# SAMD_Test_Board.net
KiCad netlist of a schematic drawn in EAGLE
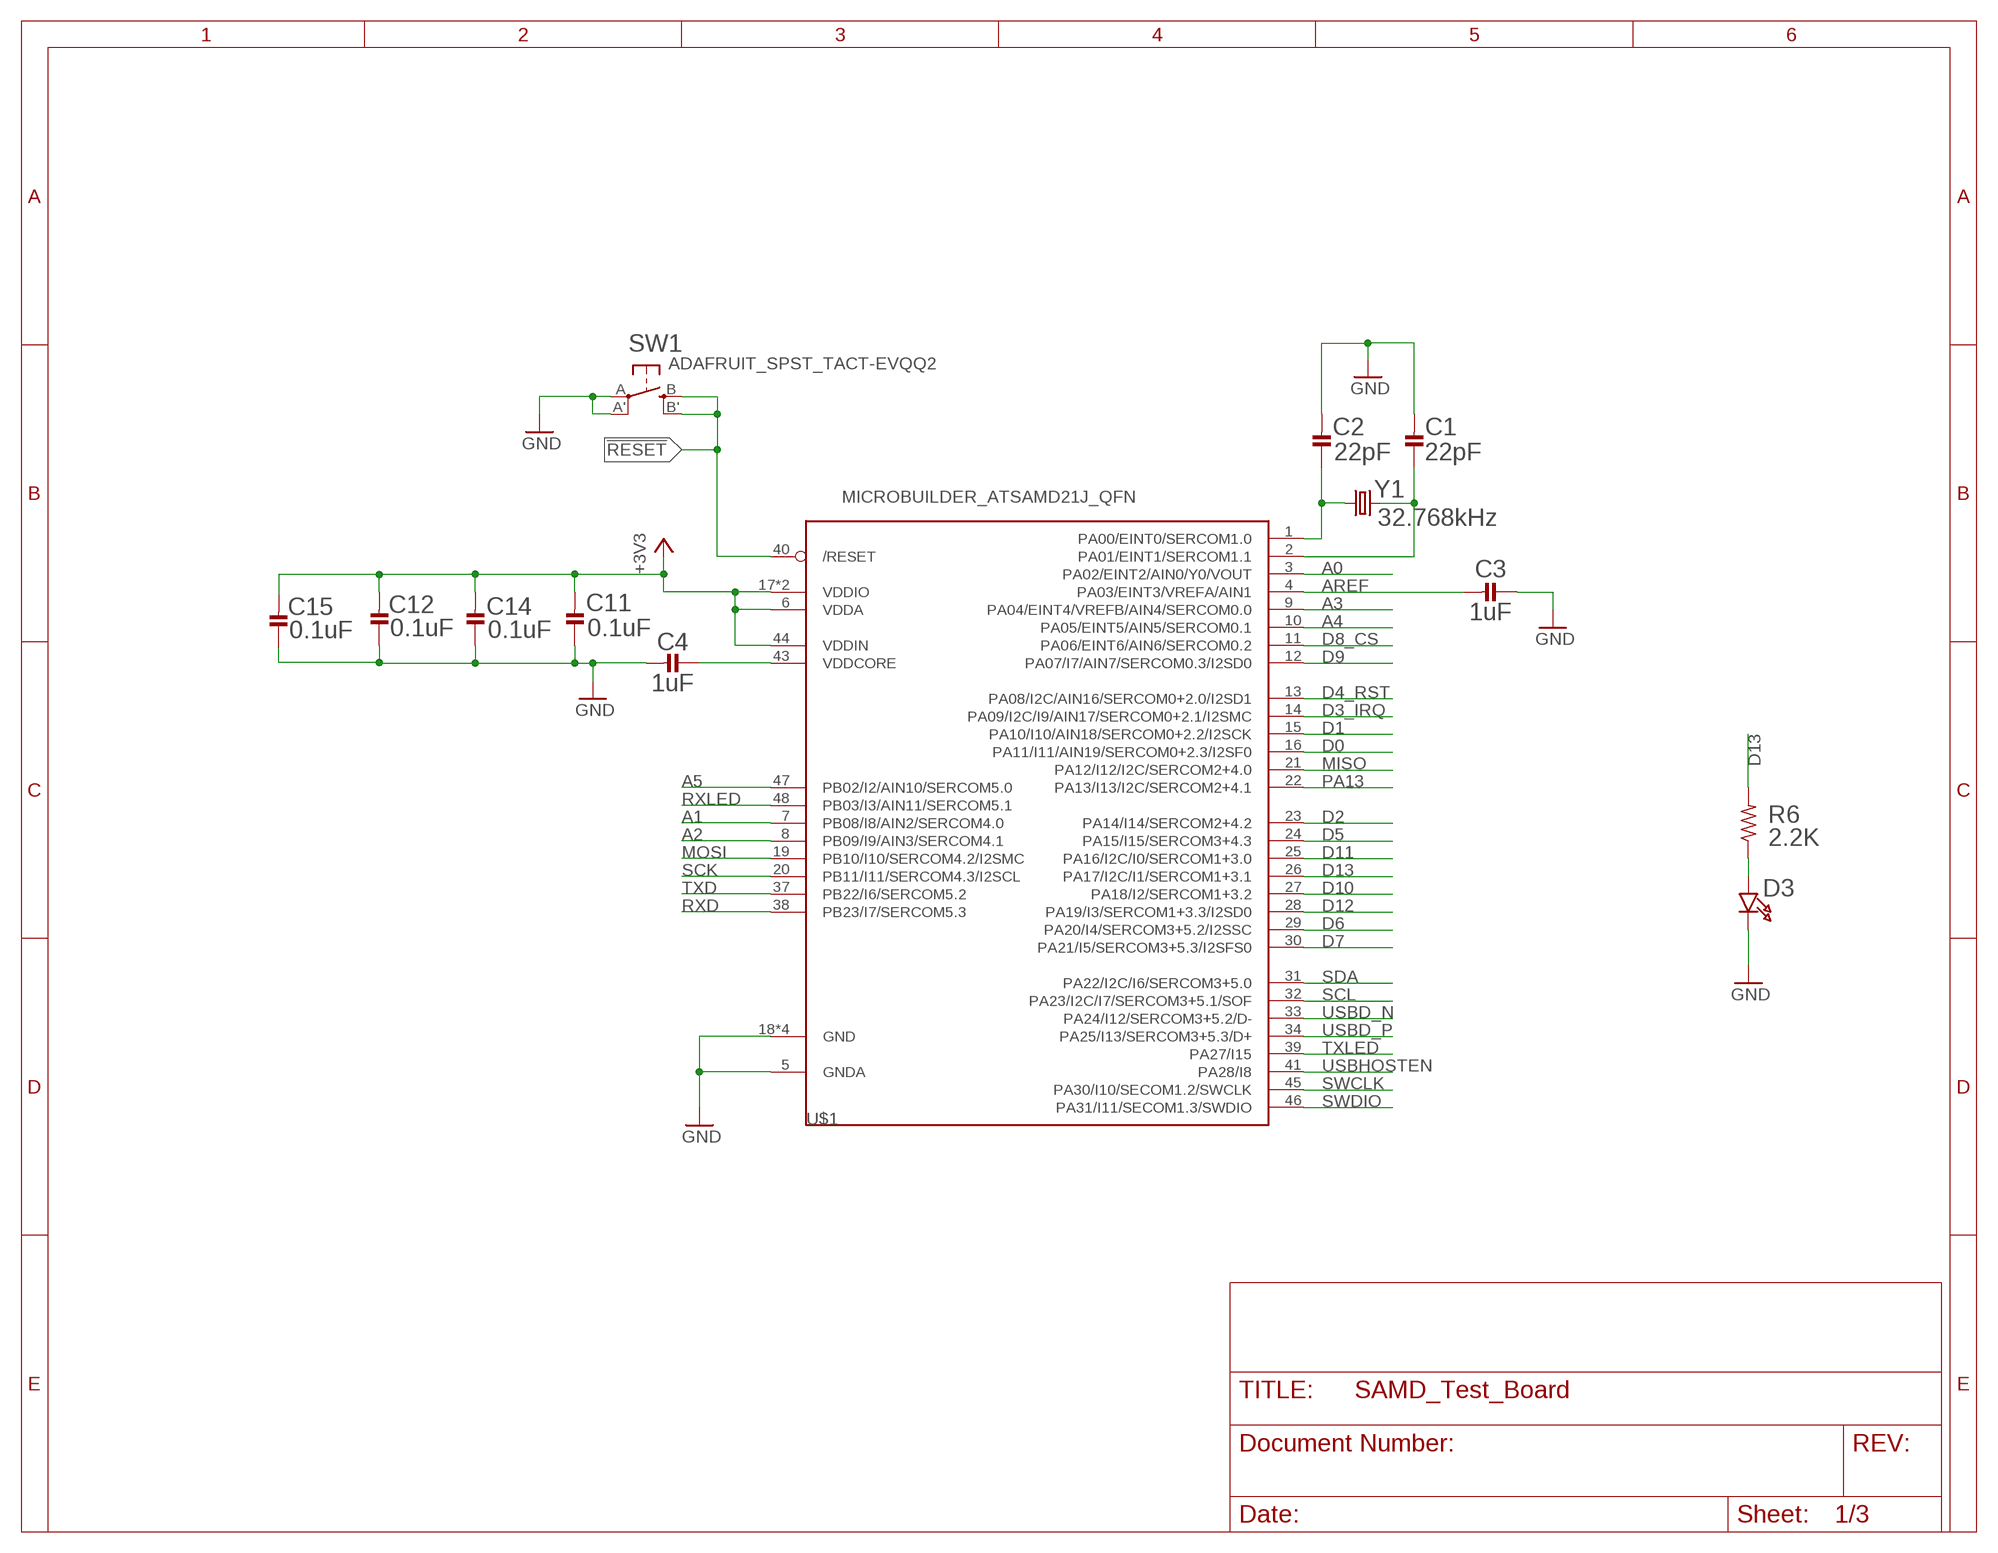
[diagram p0: schematic, sheet 1]
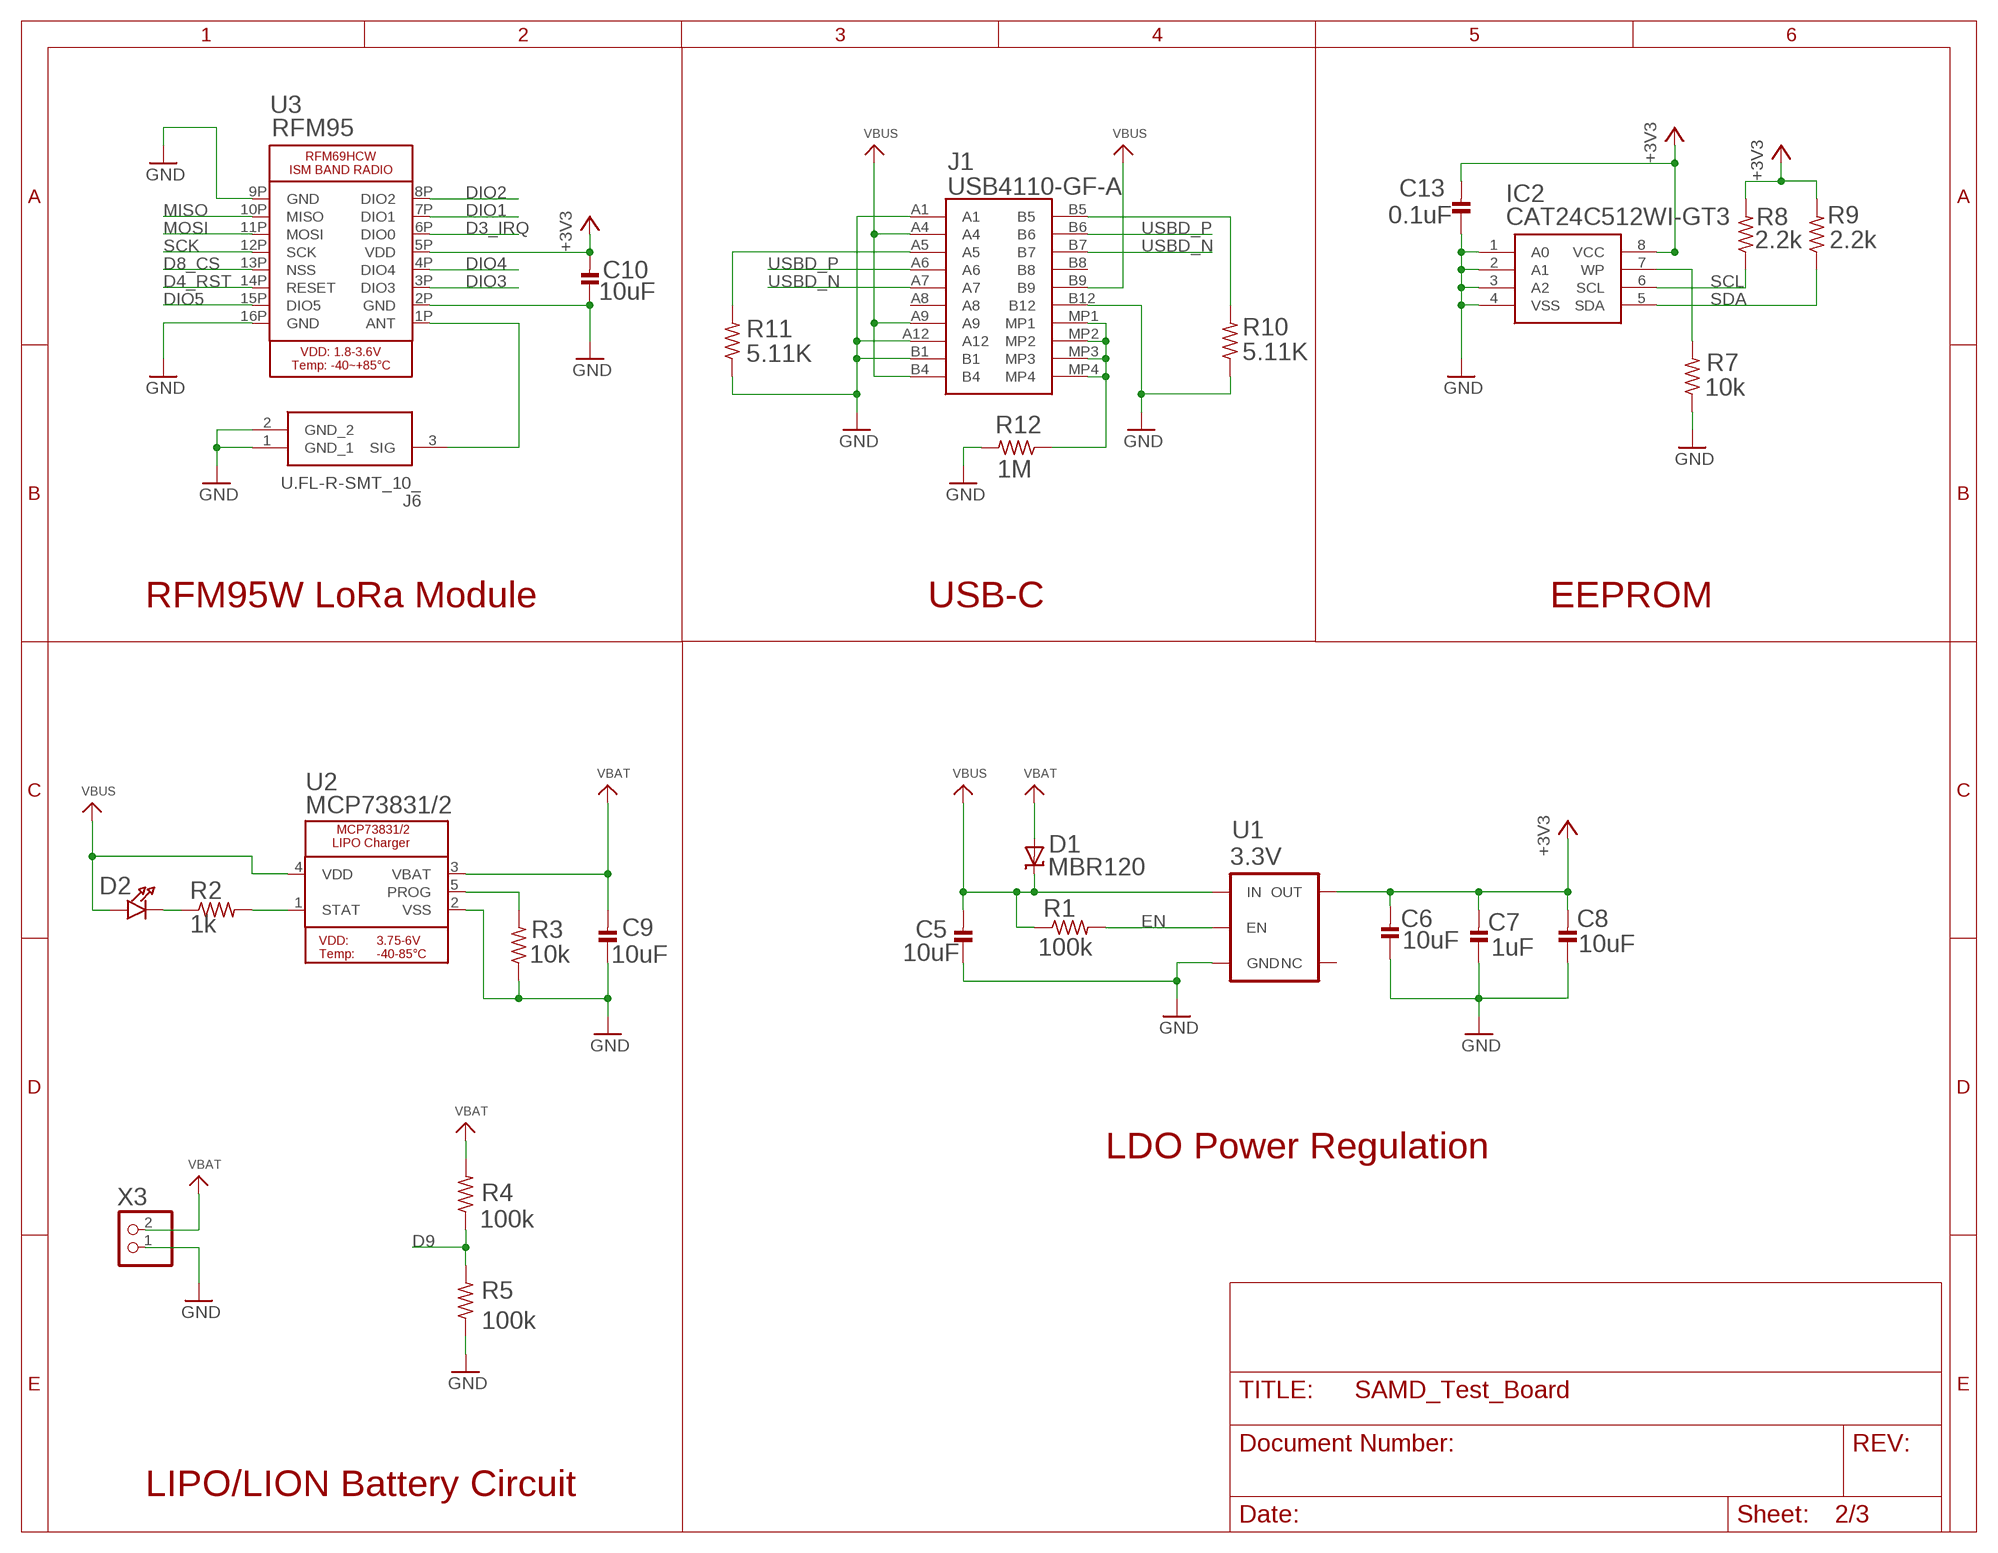
[diagram p1: schematic, sheet 2]
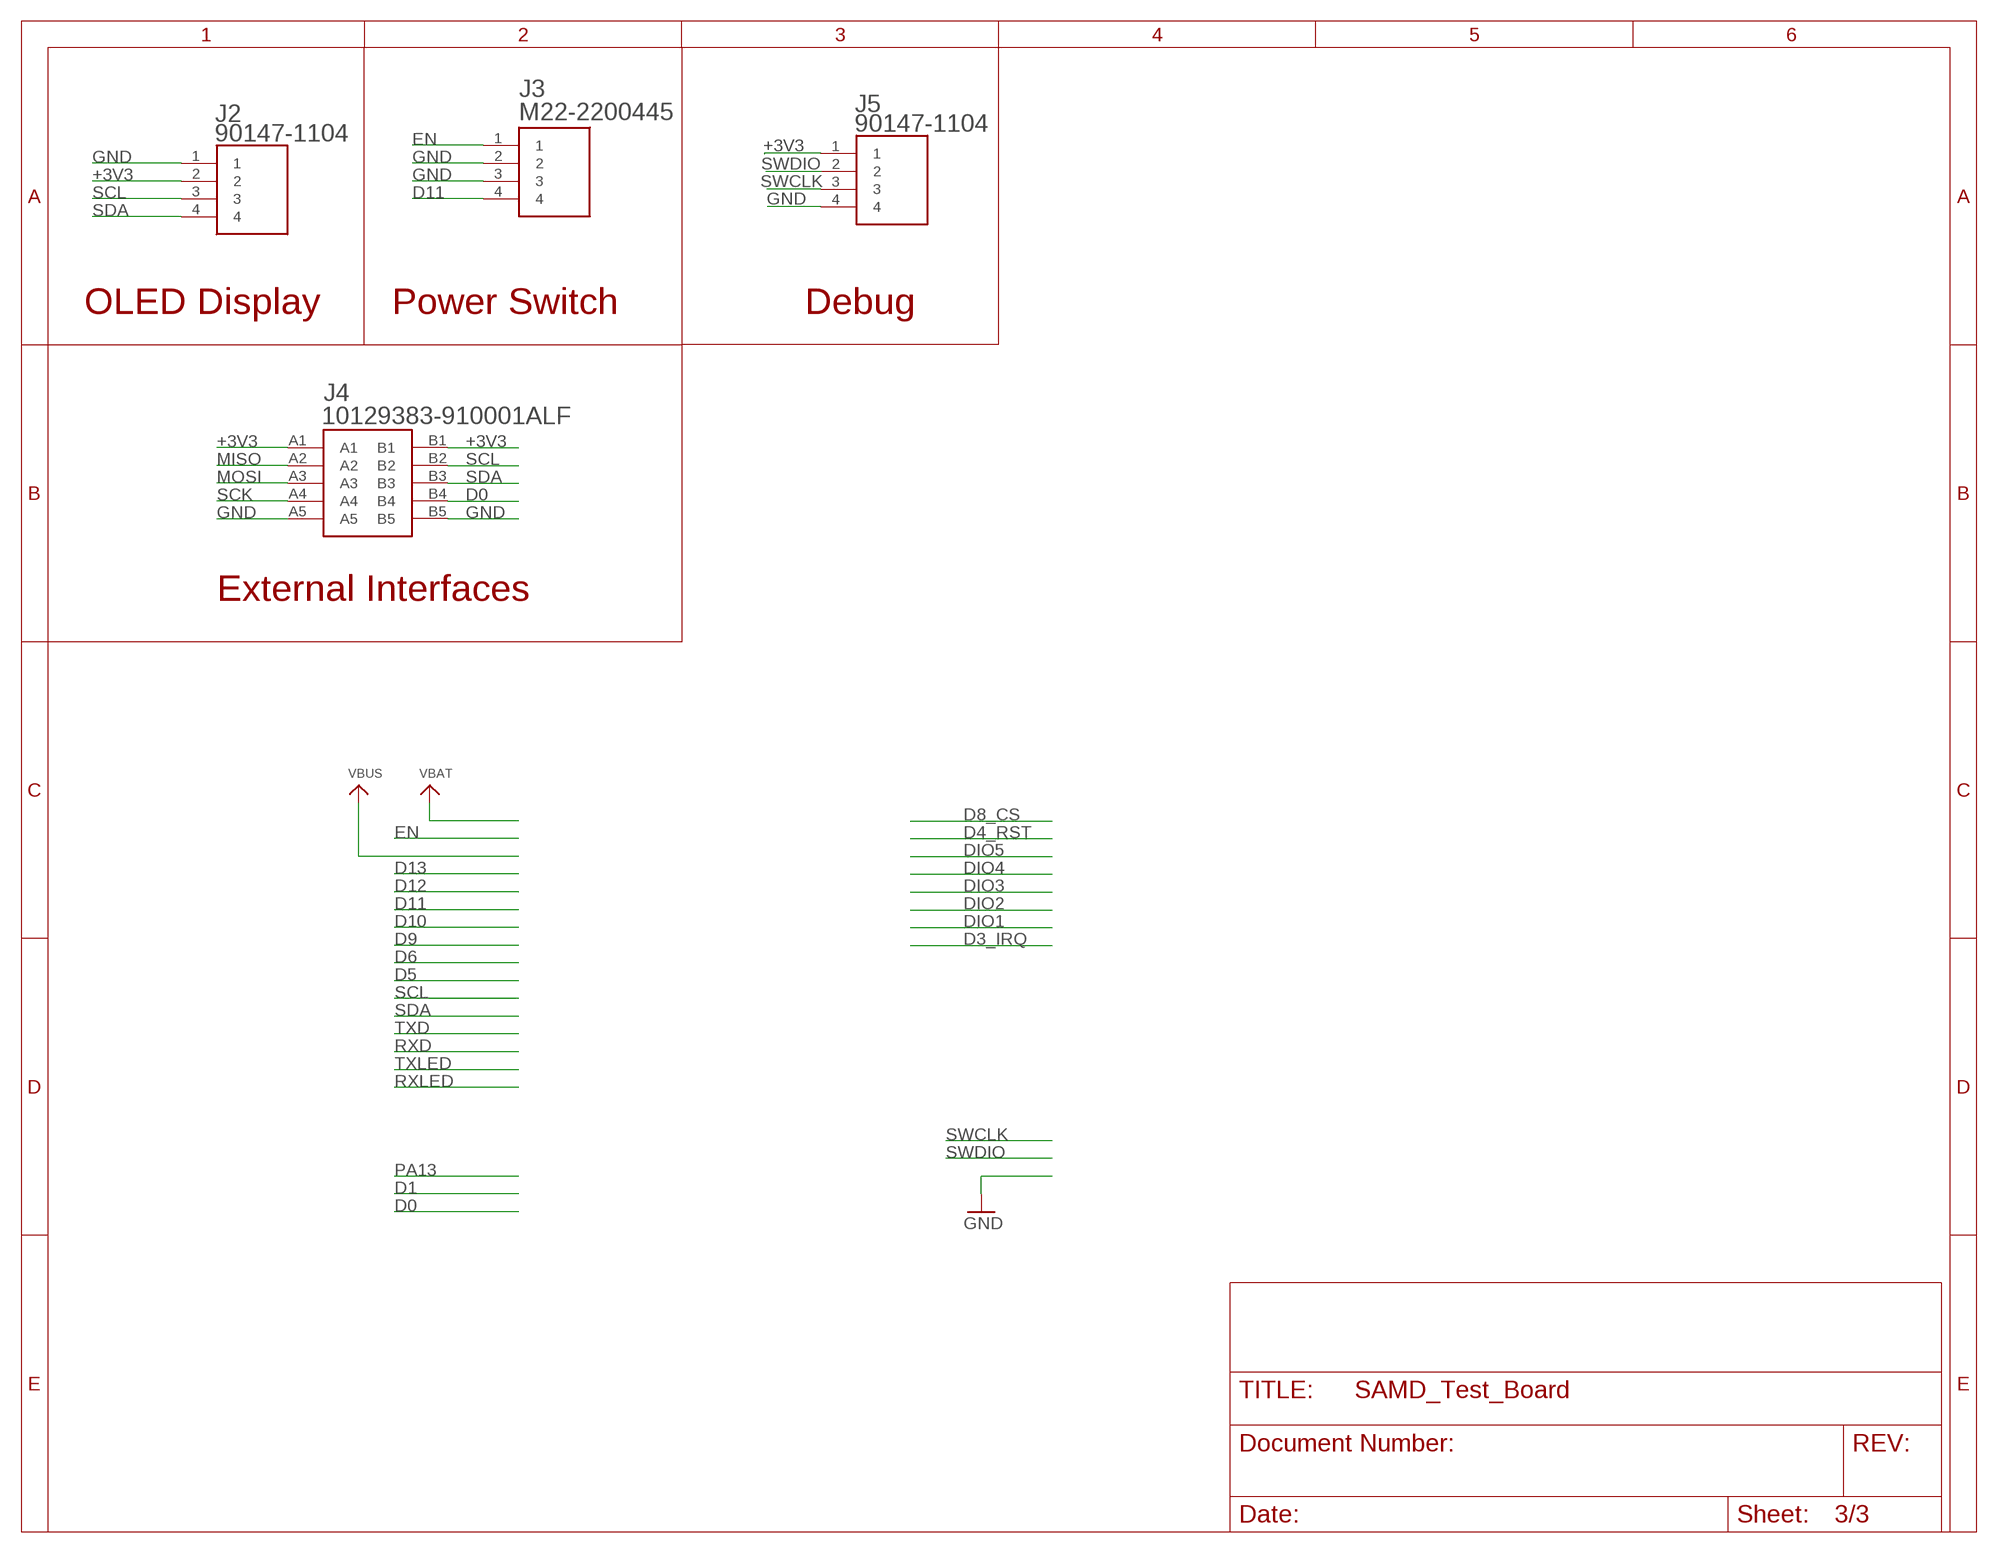
[diagram p2: schematic, sheet 3]

(export (version "E")
  (design (tool "Eeschema 10.0.6"))
  (components
    (comp (ref "C1")
      (value "22pF")
      (footprint "eagle-import:MICROBUILDER__0805")
      (libsource (lib "eagle-import") (part "MICROBUILDER_CAP_CERAMIC_0805"))
    )
    (comp (ref "C2")
      (value "22pF")
      (footprint "eagle-import:MICROBUILDER__0805")
      (libsource (lib "eagle-import") (part "MICROBUILDER_CAP_CERAMIC_0805"))
    )
    (comp (ref "C3")
      (value "1uF")
      (footprint "eagle-import:MICROBUILDER__0805")
      (libsource (lib "eagle-import") (part "MICROBUILDER_CAP_CERAMIC_0805"))
    )
    (comp (ref "C4")
      (value "1uF")
      (footprint "eagle-import:MICROBUILDER__0805")
      (libsource (lib "eagle-import") (part "MICROBUILDER_CAP_CERAMIC_0805"))
    )
    (comp (ref "C11")
      (value "0.1uF")
      (footprint "eagle-import:MICROBUILDER__0805")
      (libsource (lib "eagle-import") (part "MICROBUILDER_CAP_CERAMIC_0805"))
    )
    (comp (ref "C12")
      (value "0.1uF")
      (footprint "eagle-import:MICROBUILDER__0805")
      (libsource (lib "eagle-import") (part "MICROBUILDER_CAP_CERAMIC_0805"))
    )
    (comp (ref "C14")
      (value "0.1uF")
      (footprint "eagle-import:MICROBUILDER__0805")
      (libsource (lib "eagle-import") (part "MICROBUILDER_CAP_CERAMIC_0805"))
    )
    (comp (ref "C15")
      (value "0.1uF")
      (footprint "eagle-import:MICROBUILDER__0805")
      (libsource (lib "eagle-import") (part "MICROBUILDER_CAP_CERAMIC_0805"))
    )
    (comp (ref "D3")
      (value "MICROBUILDER_LED0603")
      (footprint "eagle-import:MICROBUILDER_CHIPLED_0603")
      (libsource (lib "eagle-import") (part "MICROBUILDER_LED0603"))
    )
    (comp (ref "R6")
      (value "2.2K")
      (footprint "eagle-import:R0805")
      (libsource (lib "eagle-import") (part "R-US_R0805"))
    )
    (comp (ref "SW1")
      (value "ADAFRUIT_SPST_TACT-EVQQ2")
      (footprint "eagle-import:ADAFRUIT_EVQ-Q2")
      (libsource (lib "eagle-import") (part "ADAFRUIT_SPST_TACT-EVQQ2"))
    )
    (comp (ref "U$1")
      (value "MICROBUILDER_ATSAMD21J_QFN")
      (footprint "eagle-import:MICROBUILDER_TQFN48_7MM")
      (libsource (lib "eagle-import") (part "MICROBUILDER_ATSAMD21J_QFN"))
    )
    (comp (ref "Y1")
      (value "32.768kHz")
      (footprint "eagle-import:CRYSTAL-SMD-3.2X1.5MM")
      (libsource (lib "eagle-import") (part "CRYSTAL-32.768KHZSMD-3.2X1.5"))
    )
    (comp (ref "C5")
      (value "10uF")
      (footprint "eagle-import:MICROBUILDER__0805")
      (libsource (lib "eagle-import") (part "MICROBUILDER_CAP_CERAMIC_0805"))
    )
    (comp (ref "C6")
      (value "10uF")
      (footprint "eagle-import:MICROBUILDER__0805")
      (libsource (lib "eagle-import") (part "MICROBUILDER_CAP_CERAMIC_0805"))
    )
    (comp (ref "C7")
      (value "1uF")
      (footprint "eagle-import:MICROBUILDER__0805")
      (libsource (lib "eagle-import") (part "MICROBUILDER_CAP_CERAMIC_0805"))
    )
    (comp (ref "C8")
      (value "10uF")
      (footprint "eagle-import:MICROBUILDER__0805")
      (libsource (lib "eagle-import") (part "MICROBUILDER_CAP_CERAMIC_0805"))
    )
    (comp (ref "C9")
      (value "10uF")
      (footprint "eagle-import:MICROBUILDER__0805")
      (libsource (lib "eagle-import") (part "MICROBUILDER_CAP_CERAMIC_0805"))
    )
    (comp (ref "C10")
      (value "10uF")
      (footprint "eagle-import:MICROBUILDER__0805")
      (libsource (lib "eagle-import") (part "MICROBUILDER_CAP_CERAMIC_0805"))
    )
    (comp (ref "C13")
      (value "0.1uF")
      (footprint "eagle-import:MICROBUILDER__0805")
      (libsource (lib "eagle-import") (part "MICROBUILDER_CAP_CERAMIC_0805"))
    )
    (comp (ref "D1")
      (value "MBR120")
      (footprint "eagle-import:MICROBUILDER_SOD-123")
      (libsource (lib "eagle-import") (part "MICROBUILDER_DIODE-SCHOTTKYSOD-123"))
    )
    (comp (ref "D2")
      (value "MICROBUILDER_LED0603")
      (footprint "eagle-import:MICROBUILDER_CHIPLED_0603")
      (libsource (lib "eagle-import") (part "MICROBUILDER_LED0603"))
    )
    (comp (ref "IC2")
      (value "CAT24C512WI-GT3")
      (footprint "eagle-import:SOIC127P600X175-8N")
      (fields (field (name "MOUSER_PART_NUMBER") "863-CAT24C512WI-GT3"))
      (libsource (lib "eagle-import") (part "CAT24C512WI-GT3"))
    )
    (comp (ref "J1")
      (value "USB4110-GF-A")
      (footprint "eagle-import:USB4110GFA")
      (fields (field (name "MOUSER_PART_NUMBER") "640-USB4110-GF-A"))
      (libsource (lib "eagle-import") (part "USB4110-GF-A"))
    )
    (comp (ref "J6")
      (value "U.FL-R-SMT_10_")
      (footprint "eagle-import:UFLRSMT10")
      (fields
        (field (name "MANUFACTURER_PART_NUMBER") "U.FL-R-SMT(10)")
        (field (name "MOUSER_PART_NUMBER") "798-U.FL-R-SMT10")
      )
      (libsource (lib "eagle-import") (part "U.FL-R-SMT_10_"))
    )
    (comp (ref "R1")
      (value "100k")
      (footprint "eagle-import:R0805")
      (libsource (lib "eagle-import") (part "R-US_R0805"))
    )
    (comp (ref "R2")
      (value "1k")
      (footprint "eagle-import:R0805")
      (libsource (lib "eagle-import") (part "R-US_R0805"))
    )
    (comp (ref "R3")
      (value "10k")
      (footprint "eagle-import:R0805")
      (libsource (lib "eagle-import") (part "R-US_R0805"))
    )
    (comp (ref "R4")
      (value "100k")
      (footprint "eagle-import:R0805")
      (libsource (lib "eagle-import") (part "R-US_R0805"))
    )
    (comp (ref "R5")
      (value "100k")
      (footprint "eagle-import:R0805")
      (libsource (lib "eagle-import") (part "R-US_R0805"))
    )
    (comp (ref "R7")
      (value "10k")
      (footprint "eagle-import:R0805")
      (libsource (lib "eagle-import") (part "R-US_R0805"))
    )
    (comp (ref "R8")
      (value "2.2k")
      (footprint "eagle-import:R0805")
      (libsource (lib "eagle-import") (part "R-US_R0805"))
    )
    (comp (ref "R9")
      (value "2.2k")
      (footprint "eagle-import:R0805")
      (libsource (lib "eagle-import") (part "R-US_R0805"))
    )
    (comp (ref "R10")
      (value "5.11K")
      (footprint "eagle-import:R0805")
      (libsource (lib "eagle-import") (part "R-US_R0805"))
    )
    (comp (ref "R11")
      (value "5.11K")
      (footprint "eagle-import:R0805")
      (libsource (lib "eagle-import") (part "R-US_R0805"))
    )
    (comp (ref "R12")
      (value "1M")
      (footprint "eagle-import:R0805")
      (libsource (lib "eagle-import") (part "R-US_R0805"))
    )
    (comp (ref "U1")
      (value "3.3V")
      (footprint "eagle-import:SOT23-5")
      (libsource (lib "eagle-import") (part "V_REG_AP2112K-3.3V"))
    )
    (comp (ref "U2")
      (value "MCP73831/2")
      (footprint "eagle-import:MICROBUILDER_SOT23-5")
      (libsource (lib "eagle-import") (part "MICROBUILDER_MCP73831/2"))
    )
    (comp (ref "U3")
      (value "RFM95")
      (footprint "eagle-import:MICROBUILDER_RFMHCW_SMT")
      (libsource (lib "eagle-import") (part "MICROBUILDER_RFM69HCW_SMT"))
    )
    (comp (ref "X3")
      (value "MICROBUILDER_CON_JST_PH_2PIN")
      (footprint "eagle-import:MICROBUILDER_JSTPH2")
      (libsource (lib "eagle-import") (part "MICROBUILDER_CON_JST_PH_2PIN"))
    )
    (comp (ref "J2")
      (value "90147-1104")
      (footprint "eagle-import:RHDR4W70P0X254_1X4_1016X244X87")
      (fields (field (name "MOUSER_PART_NUMBER") "538-90147-1104"))
      (libsource (lib "eagle-import") (part "90147-1104"))
    )
    (comp (ref "J3")
      (value "M22-2200445")
      (footprint "eagle-import:SHDR4W50P0X200_1X4_1000X470X63")
      (fields (field (name "MOUSER_PART_NUMBER") "855-M22-2200445"))
      (libsource (lib "eagle-import") (part "M22-2200445"))
    )
    (comp (ref "J4")
      (value "10129383-910001ALF")
      (footprint "eagle-import:10129383910001ALF")
      (fields (field (name "MOUSER_PART_NUMBER") "649-1012938391001ALF"))
      (libsource (lib "eagle-import") (part "10129383-910001ALF"))
    )
    (comp (ref "J5")
      (value "90147-1104")
      (footprint "eagle-import:RHDR4W70P0X254_1X4_1016X244X87")
      (fields (field (name "MOUSER_PART_NUMBER") "538-90147-1104"))
      (libsource (lib "eagle-import") (part "90147-1104"))
    )
  )
  (nets
    (net (code "1") (name "+3V3") (class "Default")
      (node (ref "C10") (pin "2") (pinfunction "2_2") (pintype "passive"))
      (node (ref "C11") (pin "2") (pinfunction "2_2") (pintype "passive"))
      (node (ref "C12") (pin "2") (pinfunction "2_2") (pintype "passive"))
      (node (ref "C13") (pin "2") (pinfunction "2_2") (pintype "passive"))
      (node (ref "C14") (pin "2") (pinfunction "2_2") (pintype "passive"))
      (node (ref "C15") (pin "2") (pinfunction "2_2") (pintype "passive"))
      (node (ref "C6") (pin "2") (pinfunction "2_2") (pintype "passive"))
      (node (ref "C7") (pin "2") (pinfunction "2_2") (pintype "passive"))
      (node (ref "C8") (pin "2") (pinfunction "2_2") (pintype "passive"))
      (node (ref "IC2") (pin "8") (pinfunction "VCC_8") (pintype "power_in"))
      (node (ref "J2") (pin "2") (pinfunction "2_2") (pintype "bidirectional"))
      (node (ref "J4") (pin "A1") (pinfunction "A1_A1") (pintype "bidirectional"))
      (node (ref "J4") (pin "B1") (pinfunction "B1_B1") (pintype "bidirectional"))
      (node (ref "J5") (pin "1") (pinfunction "1_1") (pintype "bidirectional"))
      (node (ref "R8") (pin "2") (pinfunction "2_2") (pintype "passive"))
      (node (ref "R9") (pin "2") (pinfunction "2_2") (pintype "passive"))
      (node (ref "U$1") (pin "17") (pinfunction "VDDIO_17") (pintype "power_in"))
      (node (ref "U$1") (pin "36") (pinfunction "VDDIO_36") (pintype "power_in"))
      (node (ref "U$1") (pin "44") (pinfunction "VDDIN_44") (pintype "power_in"))
      (node (ref "U$1") (pin "6") (pinfunction "VDDA_6") (pintype "power_in"))
      (node (ref "U1") (pin "5") (pinfunction "OUT_5") (pintype "passive"))
      (node (ref "U3") (pin "5P") (pinfunction "VDD_5P") (pintype "power_in"))
    )
    (net (code "2") (name "A0") (class "Default")
      (node (ref "U$1") (pin "3") (pinfunction "PA02/EINT2/AIN0/Y0/VOUT_3") (pintype "bidirectional"))
    )
    (net (code "3") (name "A1") (class "Default")
      (node (ref "U$1") (pin "7") (pinfunction "PB08/I8/AIN2/SERCOM4.0_7") (pintype "bidirectional"))
    )
    (net (code "4") (name "A2") (class "Default")
      (node (ref "U$1") (pin "8") (pinfunction "PB09/I9/AIN3/SERCOM4.1_8") (pintype "bidirectional"))
    )
    (net (code "5") (name "A3") (class "Default")
      (node (ref "U$1") (pin "9") (pinfunction "PA04/EINT4/VREFB/AIN4/SERCOM0.0_9") (pintype "bidirectional"))
    )
    (net (code "6") (name "A4") (class "Default")
      (node (ref "U$1") (pin "10") (pinfunction "PA05/EINT5/AIN5/SERCOM0.1_10") (pintype "bidirectional"))
    )
    (net (code "7") (name "A5") (class "Default")
      (node (ref "U$1") (pin "47") (pinfunction "PB02/I2/AIN10/SERCOM5.0_47") (pintype "bidirectional"))
    )
    (net (code "8") (name "AREF") (class "Default")
      (node (ref "C3") (pin "2") (pinfunction "2_2") (pintype "passive"))
      (node (ref "U$1") (pin "4") (pinfunction "PA03/EINT3/VREFA/AIN1_4") (pintype "bidirectional"))
    )
    (net (code "9") (name "D0") (class "Default")
      (node (ref "J4") (pin "B4") (pinfunction "B4_B4") (pintype "bidirectional"))
      (node (ref "U$1") (pin "16") (pinfunction "PA11/I11/AIN19/SERCOM0+2.3/I2SF0_16") (pintype "bidirectional"))
    )
    (net (code "10") (name "D1") (class "Default")
      (node (ref "U$1") (pin "15") (pinfunction "PA10/I10/AIN18/SERCOM0+2.2/I2SCK_15") (pintype "bidirectional"))
    )
    (net (code "11") (name "D2") (class "Default")
      (node (ref "U$1") (pin "23") (pinfunction "PA14/I14/SERCOM2+4.2_23") (pintype "bidirectional"))
    )
    (net (code "12") (name "D3_IRQ") (class "Default")
      (node (ref "U$1") (pin "14") (pinfunction "PA09/I2C/I9/AIN17/SERCOM0+2.1/I2SMC_14") (pintype "bidirectional"))
      (node (ref "U3") (pin "6P") (pinfunction "DIO0_6P") (pintype "bidirectional"))
    )
    (net (code "13") (name "D4_RST") (class "Default")
      (node (ref "U$1") (pin "13") (pinfunction "PA08/I2C/AIN16/SERCOM0+2.0/I2SD1_13") (pintype "bidirectional"))
      (node (ref "U3") (pin "14P") (pinfunction "RESET_14P") (pintype "input"))
    )
    (net (code "14") (name "D5") (class "Default")
      (node (ref "U$1") (pin "24") (pinfunction "PA15/I15/SERCOM3+4.3_24") (pintype "bidirectional"))
    )
    (net (code "15") (name "D6") (class "Default")
      (node (ref "U$1") (pin "29") (pinfunction "PA20/I4/SERCOM3+5.2/I2SSC_29") (pintype "bidirectional"))
    )
    (net (code "16") (name "D7") (class "Default")
      (node (ref "U$1") (pin "30") (pinfunction "PA21/I5/SERCOM3+5.3/I2SFS0_30") (pintype "bidirectional"))
    )
    (net (code "17") (name "D8_CS") (class "Default")
      (node (ref "U$1") (pin "11") (pinfunction "PA06/EINT6/AIN6/SERCOM0.2_11") (pintype "bidirectional"))
      (node (ref "U3") (pin "13P") (pinfunction "NSS_13P") (pintype "input"))
    )
    (net (code "18") (name "D9") (class "Default")
      (node (ref "R4") (pin "1") (pinfunction "1_1") (pintype "passive"))
      (node (ref "R5") (pin "2") (pinfunction "2_2") (pintype "passive"))
      (node (ref "U$1") (pin "12") (pinfunction "PA07/I7/AIN7/SERCOM0.3/I2SD0_12") (pintype "bidirectional"))
    )
    (net (code "19") (name "D10") (class "Default")
      (node (ref "U$1") (pin "27") (pinfunction "PA18/I2/SERCOM1+3.2_27") (pintype "bidirectional"))
    )
    (net (code "20") (name "D11") (class "Default")
      (node (ref "J3") (pin "4") (pinfunction "4_4") (pintype "bidirectional"))
      (node (ref "U$1") (pin "25") (pinfunction "PA16/I2C/I0/SERCOM1+3.0_25") (pintype "bidirectional"))
    )
    (net (code "21") (name "D12") (class "Default")
      (node (ref "U$1") (pin "28") (pinfunction "PA19/I3/SERCOM1+3.3/I2SD0_28") (pintype "bidirectional"))
    )
    (net (code "22") (name "D13") (class "Default")
      (node (ref "R6") (pin "2") (pinfunction "2_2") (pintype "passive"))
      (node (ref "U$1") (pin "26") (pinfunction "PA17/I2C/I1/SERCOM1+3.1_26") (pintype "bidirectional"))
    )
    (net (code "23") (name "DIO1") (class "Default")
      (node (ref "U3") (pin "7P") (pinfunction "DIO1_7P") (pintype "bidirectional"))
    )
    (net (code "24") (name "DIO2") (class "Default")
      (node (ref "U3") (pin "8P") (pinfunction "DIO2_8P") (pintype "bidirectional"))
    )
    (net (code "25") (name "DIO3") (class "Default")
      (node (ref "U3") (pin "3P") (pinfunction "DIO3_3P") (pintype "bidirectional"))
    )
    (net (code "26") (name "DIO4") (class "Default")
      (node (ref "U3") (pin "4P") (pinfunction "DIO4_4P") (pintype "bidirectional"))
    )
    (net (code "27") (name "DIO5") (class "Default")
      (node (ref "U3") (pin "15P") (pinfunction "DIO5_15P") (pintype "bidirectional"))
    )
    (net (code "28") (name "EN") (class "Default")
      (node (ref "J3") (pin "1") (pinfunction "1_1") (pintype "bidirectional"))
      (node (ref "R1") (pin "2") (pinfunction "2_2") (pintype "passive"))
      (node (ref "U1") (pin "3") (pinfunction "EN_3") (pintype "input"))
    )
    (net (code "29") (name "GND") (class "Default")
      (node (ref "C1") (pin "2") (pinfunction "2_2") (pintype "passive"))
      (node (ref "C10") (pin "1") (pinfunction "1_1") (pintype "passive"))
      (node (ref "C11") (pin "1") (pinfunction "1_1") (pintype "passive"))
      (node (ref "C12") (pin "1") (pinfunction "1_1") (pintype "passive"))
      (node (ref "C13") (pin "1") (pinfunction "1_1") (pintype "passive"))
      (node (ref "C14") (pin "1") (pinfunction "1_1") (pintype "passive"))
      (node (ref "C15") (pin "1") (pinfunction "1_1") (pintype "passive"))
      (node (ref "C2") (pin "2") (pinfunction "2_2") (pintype "passive"))
      (node (ref "C3") (pin "1") (pinfunction "1_1") (pintype "passive"))
      (node (ref "C4") (pin "2") (pinfunction "2_2") (pintype "passive"))
      (node (ref "C5") (pin "1") (pinfunction "1_1") (pintype "passive"))
      (node (ref "C6") (pin "1") (pinfunction "1_1") (pintype "passive"))
      (node (ref "C7") (pin "1") (pinfunction "1_1") (pintype "passive"))
      (node (ref "C8") (pin "1") (pinfunction "1_1") (pintype "passive"))
      (node (ref "C9") (pin "1") (pinfunction "1_1") (pintype "passive"))
      (node (ref "D3") (pin "C") (pinfunction "C_C") (pintype "passive"))
      (node (ref "IC2") (pin "1") (pinfunction "A0_1") (pintype "bidirectional"))
      (node (ref "IC2") (pin "2") (pinfunction "A1_2") (pintype "bidirectional"))
      (node (ref "IC2") (pin "3") (pinfunction "A2_3") (pintype "bidirectional"))
      (node (ref "IC2") (pin "4") (pinfunction "VSS_4") (pintype "power_in"))
      (node (ref "J1") (pin "A1") (pinfunction "A1_A1") (pintype "bidirectional"))
      (node (ref "J1") (pin "A12") (pinfunction "A12_A12") (pintype "bidirectional"))
      (node (ref "J1") (pin "B1") (pinfunction "B1_B1") (pintype "bidirectional"))
      (node (ref "J1") (pin "B12") (pinfunction "B12_B12") (pintype "bidirectional"))
      (node (ref "J2") (pin "1") (pinfunction "1_1") (pintype "bidirectional"))
      (node (ref "J3") (pin "2") (pinfunction "2_2") (pintype "bidirectional"))
      (node (ref "J3") (pin "3") (pinfunction "3_3") (pintype "bidirectional"))
      (node (ref "J4") (pin "A5") (pinfunction "A5_A5") (pintype "bidirectional"))
      (node (ref "J4") (pin "B5") (pinfunction "B5_B5") (pintype "bidirectional"))
      (node (ref "J5") (pin "4") (pinfunction "4_4") (pintype "bidirectional"))
      (node (ref "J6") (pin "1") (pinfunction "GND_1_1") (pintype "bidirectional"))
      (node (ref "J6") (pin "2") (pinfunction "GND_2_2") (pintype "bidirectional"))
      (node (ref "R10") (pin "1") (pinfunction "1_1") (pintype "passive"))
      (node (ref "R11") (pin "1") (pinfunction "1_1") (pintype "passive"))
      (node (ref "R12") (pin "2") (pinfunction "2_2") (pintype "passive"))
      (node (ref "R3") (pin "1") (pinfunction "1_1") (pintype "passive"))
      (node (ref "R5") (pin "1") (pinfunction "1_1") (pintype "passive"))
      (node (ref "R7") (pin "1") (pinfunction "1_1") (pintype "passive"))
      (node (ref "SW1") (pin "A") (pinfunction "P_A") (pintype "passive"))
      (node (ref "SW1") (pin "A'") (pinfunction "P1_A'") (pintype "passive"))
      (node (ref "U$1") (pin "18") (pinfunction "GND_18") (pintype "power_in"))
      (node (ref "U$1") (pin "35") (pinfunction "GND_35") (pintype "power_in"))
      (node (ref "U$1") (pin "42") (pinfunction "GND_42") (pintype "power_in"))
      (node (ref "U$1") (pin "5") (pinfunction "GNDA_5") (pintype "power_in"))
      (node (ref "U$1") (pin "THERMAL") (pinfunction "GND_THERMAL") (pintype "power_in"))
      (node (ref "U1") (pin "2") (pinfunction "GND_2") (pintype "input"))
      (node (ref "U2") (pin "2") (pinfunction "VSS_2") (pintype "power_in"))
      (node (ref "U3") (pin "16P") (pinfunction "GND_16P") (pintype "power_in"))
      (node (ref "U3") (pin "2P") (pinfunction "GND_2P") (pintype "power_in"))
      (node (ref "U3") (pin "9P") (pinfunction "GND_9P") (pintype "power_in"))
      (node (ref "X3") (pin "1") (pinfunction "1_1") (pintype "passive"))
    )
    (net (code "30") (name "MISO") (class "Default")
      (node (ref "J4") (pin "A2") (pinfunction "A2_A2") (pintype "bidirectional"))
      (node (ref "U$1") (pin "21") (pinfunction "PA12/I12/I2C/SERCOM2+4.0_21") (pintype "bidirectional"))
      (node (ref "U3") (pin "10P") (pinfunction "MISO_10P") (pintype "output"))
    )
    (net (code "31") (name "MOSI") (class "Default")
      (node (ref "J4") (pin "A3") (pinfunction "A3_A3") (pintype "bidirectional"))
      (node (ref "U$1") (pin "19") (pinfunction "PB10/I10/SERCOM4.2/I2SMC_19") (pintype "bidirectional"))
      (node (ref "U3") (pin "11P") (pinfunction "MOSI_11P") (pintype "input"))
    )
    (net (code "32") (name "Net-(D2-PadC)") (class "Default")
      (node (ref "D2") (pin "C") (pinfunction "C_C") (pintype "passive"))
      (node (ref "R2") (pin "1") (pinfunction "1_1") (pintype "passive"))
    )
    (net (code "33") (name "Net-(D3-PadA)") (class "Default")
      (node (ref "D3") (pin "A") (pinfunction "A_A") (pintype "passive"))
      (node (ref "R6") (pin "1") (pinfunction "1_1") (pintype "passive"))
    )
    (net (code "34") (name "Net-(IC2-WP)") (class "Default")
      (node (ref "IC2") (pin "7") (pinfunction "WP_7") (pintype "bidirectional"))
      (node (ref "R7") (pin "2") (pinfunction "2_2") (pintype "passive"))
    )
    (net (code "35") (name "Net-(J1-PadA5)") (class "Default")
      (node (ref "J1") (pin "A5") (pinfunction "A5_A5") (pintype "bidirectional"))
      (node (ref "R11") (pin "2") (pinfunction "2_2") (pintype "passive"))
    )
    (net (code "36") (name "Net-(J1-PadB5)") (class "Default")
      (node (ref "J1") (pin "B5") (pinfunction "B5_B5") (pintype "bidirectional"))
      (node (ref "R10") (pin "2") (pinfunction "2_2") (pintype "passive"))
    )
    (net (code "37") (name "Net-(J1-PadMP1)") (class "Default")
      (node (ref "J1") (pin "MP1") (pinfunction "MP1_MP1") (pintype "bidirectional"))
      (node (ref "J1") (pin "MP2") (pinfunction "MP2_MP2") (pintype "bidirectional"))
      (node (ref "J1") (pin "MP3") (pinfunction "MP3_MP3") (pintype "bidirectional"))
      (node (ref "J1") (pin "MP4") (pinfunction "MP4_MP4") (pintype "bidirectional"))
      (node (ref "R12") (pin "1") (pinfunction "1_1") (pintype "passive"))
    )
    (net (code "38") (name "Net-(J6-SIG)") (class "Default")
      (node (ref "J6") (pin "3") (pinfunction "SIG_3") (pintype "bidirectional"))
      (node (ref "U3") (pin "1P") (pinfunction "ANT_1P") (pintype "bidirectional"))
    )
    (net (code "39") (name "Net-(U$1-PA00{slash}EINT0{slash}SERCOM1.0)") (class "Default")
      (node (ref "C2") (pin "1") (pinfunction "1_1") (pintype "passive"))
      (node (ref "U$1") (pin "1") (pinfunction "PA00/EINT0/SERCOM1.0_1") (pintype "bidirectional"))
      (node (ref "Y1") (pin "P$1") (pinfunction "1_P$1") (pintype "passive"))
    )
    (net (code "40") (name "Net-(U$1-PA01{slash}EINT1{slash}SERCOM1.1)") (class "Default")
      (node (ref "C1") (pin "1") (pinfunction "1_1") (pintype "passive"))
      (node (ref "U$1") (pin "2") (pinfunction "PA01/EINT1/SERCOM1.1_2") (pintype "bidirectional"))
      (node (ref "Y1") (pin "P$2") (pinfunction "2_P$2") (pintype "passive"))
    )
    (net (code "41") (name "Net-(U$1-VDDCORE)") (class "Default")
      (node (ref "C4") (pin "1") (pinfunction "1_1") (pintype "passive"))
      (node (ref "U$1") (pin "43") (pinfunction "VDDCORE_43") (pintype "power_in"))
    )
    (net (code "42") (name "Net-(U2-PROG)") (class "Default")
      (node (ref "R3") (pin "2") (pinfunction "2_2") (pintype "passive"))
      (node (ref "U2") (pin "5") (pinfunction "PROG_5") (pintype "input"))
    )
    (net (code "43") (name "Net-(U2-STAT)") (class "Default")
      (node (ref "R2") (pin "2") (pinfunction "2_2") (pintype "passive"))
      (node (ref "U2") (pin "1") (pinfunction "STAT_1") (pintype "output"))
    )
    (net (code "44") (name "PA13") (class "Default")
      (node (ref "U$1") (pin "22") (pinfunction "PA13/I13/I2C/SERCOM2+4.1_22") (pintype "bidirectional"))
    )
    (net (code "45") (name "RXD") (class "Default")
      (node (ref "U$1") (pin "38") (pinfunction "PB23/I7/SERCOM5.3_38") (pintype "bidirectional"))
    )
    (net (code "46") (name "RXLED") (class "Default")
      (node (ref "U$1") (pin "48") (pinfunction "PB03/I3/AIN11/SERCOM5.1_48") (pintype "bidirectional"))
    )
    (net (code "47") (name "SCK") (class "Default")
      (node (ref "J4") (pin "A4") (pinfunction "A4_A4") (pintype "bidirectional"))
      (node (ref "U$1") (pin "20") (pinfunction "PB11/I11/SERCOM4.3/I2SCL_20") (pintype "bidirectional"))
      (node (ref "U3") (pin "12P") (pinfunction "SCK_12P") (pintype "input"))
    )
    (net (code "48") (name "SCL") (class "Default")
      (node (ref "IC2") (pin "6") (pinfunction "SCL_6") (pintype "bidirectional"))
      (node (ref "J2") (pin "3") (pinfunction "3_3") (pintype "bidirectional"))
      (node (ref "J4") (pin "B2") (pinfunction "B2_B2") (pintype "bidirectional"))
      (node (ref "R8") (pin "1") (pinfunction "1_1") (pintype "passive"))
      (node (ref "U$1") (pin "32") (pinfunction "PA23/I2C/I7/SERCOM3+5.1/SOF_32") (pintype "bidirectional"))
    )
    (net (code "49") (name "SDA") (class "Default")
      (node (ref "IC2") (pin "5") (pinfunction "SDA_5") (pintype "bidirectional"))
      (node (ref "J2") (pin "4") (pinfunction "4_4") (pintype "bidirectional"))
      (node (ref "J4") (pin "B3") (pinfunction "B3_B3") (pintype "bidirectional"))
      (node (ref "R9") (pin "1") (pinfunction "1_1") (pintype "passive"))
      (node (ref "U$1") (pin "31") (pinfunction "PA22/I2C/I6/SERCOM3+5.0_31") (pintype "bidirectional"))
    )
    (net (code "50") (name "SWCLK") (class "Default")
      (node (ref "J5") (pin "3") (pinfunction "3_3") (pintype "bidirectional"))
      (node (ref "U$1") (pin "45") (pinfunction "PA30/I10/SECOM1.2/SWCLK_45") (pintype "bidirectional"))
    )
    (net (code "51") (name "SWDIO") (class "Default")
      (node (ref "J5") (pin "2") (pinfunction "2_2") (pintype "bidirectional"))
      (node (ref "U$1") (pin "46") (pinfunction "PA31/I11/SECOM1.3/SWDIO_46") (pintype "bidirectional"))
    )
    (net (code "52") (name "TXD") (class "Default")
      (node (ref "U$1") (pin "37") (pinfunction "PB22/I6/SERCOM5.2_37") (pintype "bidirectional"))
    )
    (net (code "53") (name "TXLED") (class "Default")
      (node (ref "U$1") (pin "39") (pinfunction "PA27/I15_39") (pintype "bidirectional"))
    )
    (net (code "54") (name "USBD_N") (class "Default")
      (node (ref "J1") (pin "A7") (pinfunction "A7_A7") (pintype "bidirectional"))
      (node (ref "J1") (pin "B7") (pinfunction "B7_B7") (pintype "bidirectional"))
      (node (ref "U$1") (pin "33") (pinfunction "PA24/I12/SERCOM3+5.2/D-_33") (pintype "bidirectional"))
    )
    (net (code "55") (name "USBD_P") (class "Default")
      (node (ref "J1") (pin "A6") (pinfunction "A6_A6") (pintype "bidirectional"))
      (node (ref "J1") (pin "B6") (pinfunction "B6_B6") (pintype "bidirectional"))
      (node (ref "U$1") (pin "34") (pinfunction "PA25/I13/SERCOM3+5.3/D+_34") (pintype "bidirectional"))
    )
    (net (code "56") (name "USBHOSTEN") (class "Default")
      (node (ref "U$1") (pin "41") (pinfunction "PA28/I8_41") (pintype "bidirectional"))
    )
    (net (code "57") (name "VBAT") (class "Default")
      (node (ref "C9") (pin "2") (pinfunction "2_2") (pintype "passive"))
      (node (ref "D1") (pin "A") (pinfunction "A_A") (pintype "passive"))
      (node (ref "R4") (pin "2") (pinfunction "2_2") (pintype "passive"))
      (node (ref "U2") (pin "3") (pinfunction "VBAT_3") (pintype "power_in"))
      (node (ref "X3") (pin "2") (pinfunction "2_2") (pintype "passive"))
    )
    (net (code "58") (name "VBUS") (class "Default")
      (node (ref "C5") (pin "2") (pinfunction "2_2") (pintype "passive"))
      (node (ref "D1") (pin "C") (pinfunction "C_C") (pintype "passive"))
      (node (ref "D2") (pin "A") (pinfunction "A_A") (pintype "passive"))
      (node (ref "J1") (pin "A4") (pinfunction "A4_A4") (pintype "bidirectional"))
      (node (ref "J1") (pin "A9") (pinfunction "A9_A9") (pintype "bidirectional"))
      (node (ref "J1") (pin "B4") (pinfunction "B4_B4") (pintype "bidirectional"))
      (node (ref "J1") (pin "B9") (pinfunction "B9_B9") (pintype "bidirectional"))
      (node (ref "R1") (pin "1") (pinfunction "1_1") (pintype "passive"))
      (node (ref "U1") (pin "1") (pinfunction "IN_1") (pintype "input"))
      (node (ref "U2") (pin "4") (pinfunction "VDD_4") (pintype "power_in"))
    )
    (net (code "59") (name "unconnected-(J1-PadA8)") (class "Default")
      (node (ref "J1") (pin "A8") (pinfunction "A8_A8") (pintype "bidirectional"))
    )
    (net (code "60") (name "unconnected-(J1-PadB8)") (class "Default")
      (node (ref "J1") (pin "B8") (pinfunction "B8_B8") (pintype "bidirectional"))
    )
    (net (code "61") (name "unconnected-(U1-NC-Pad4)") (class "Default")
      (node (ref "U1") (pin "4") (pinfunction "NC_4") (pintype "no_connect"))
    )
    (net (code "62") (name "~{RESET}") (class "Default")
      (node (ref "SW1") (pin "B") (pinfunction "S_B") (pintype "passive"))
      (node (ref "SW1") (pin "B'") (pinfunction "S1_B'") (pintype "passive"))
      (node (ref "U$1") (pin "40") (pinfunction "/RESET_40") (pintype "bidirectional"))
    )
  )
)
